# Header.net
KiCad netlist of a schematic drawn in Altium Designer
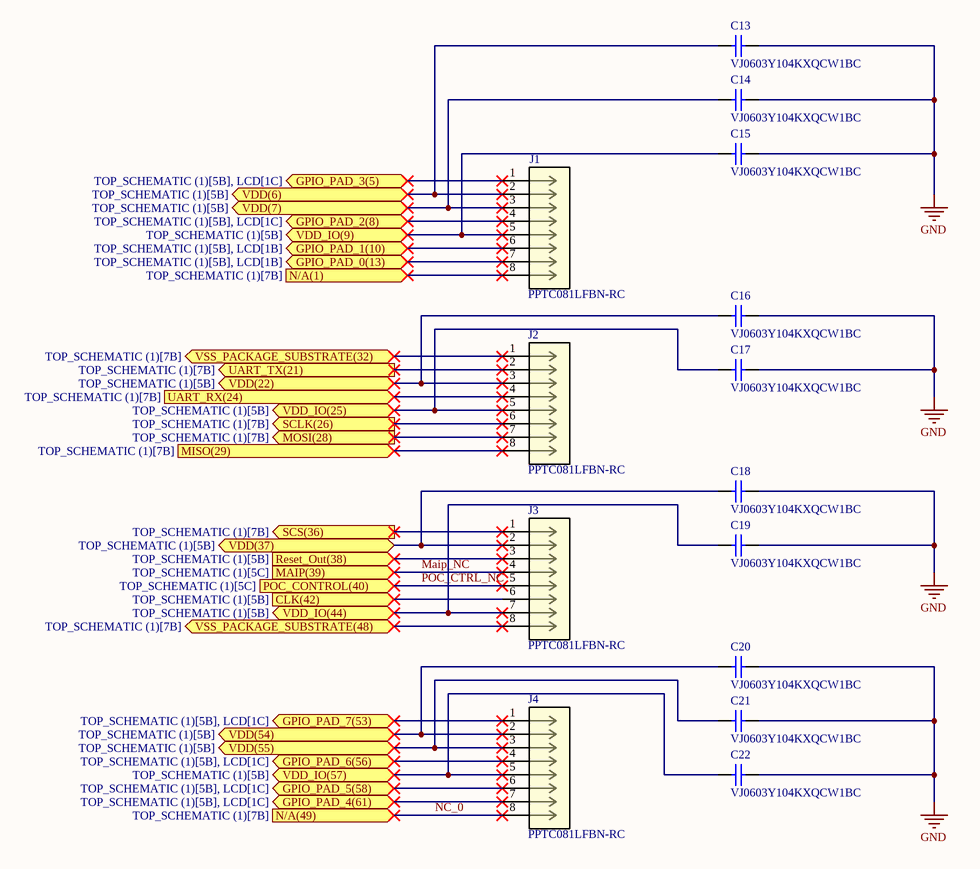
[diagram p0: Header.SchDoc]

(export (version "E")
  (design (tool "Eeschema 10.0.6"))
  (components
    (comp (ref "C13")
      (value "VJ0603Y104KXQCW1BC")
      (footprint "CAPC1608X95X40NL15T15")
      (fields (field (name "MANUFACTURER") "Vitramon"))
      (libsource (lib "Altium Content Vault") (part "CAP"))
    )
    (comp (ref "C14")
      (value "VJ0603Y104KXQCW1BC")
      (footprint "CAPC1608X95X40NL15T15")
      (fields (field (name "MANUFACTURER") "Vitramon"))
      (libsource (lib "Altium Content Vault") (part "CAP"))
    )
    (comp (ref "C15")
      (value "VJ0603Y104KXQCW1BC")
      (footprint "CAPC1608X95X40NL15T15")
      (fields (field (name "MANUFACTURER") "Vitramon"))
      (libsource (lib "Altium Content Vault") (part "CAP"))
    )
    (comp (ref "C16")
      (value "VJ0603Y104KXQCW1BC")
      (footprint "CAPC1608X95X40NL15T15")
      (fields (field (name "MANUFACTURER") "Vitramon"))
      (libsource (lib "Altium Content Vault") (part "CAP"))
    )
    (comp (ref "C17")
      (value "VJ0603Y104KXQCW1BC")
      (footprint "CAPC1608X95X40NL15T15")
      (fields (field (name "MANUFACTURER") "Vitramon"))
      (libsource (lib "Altium Content Vault") (part "CAP"))
    )
    (comp (ref "C18")
      (value "VJ0603Y104KXQCW1BC")
      (footprint "CAPC1608X95X40NL15T15")
      (fields (field (name "MANUFACTURER") "Vitramon"))
      (libsource (lib "Altium Content Vault") (part "CAP"))
    )
    (comp (ref "C19")
      (value "VJ0603Y104KXQCW1BC")
      (footprint "CAPC1608X95X40NL15T15")
      (fields (field (name "MANUFACTURER") "Vitramon"))
      (libsource (lib "Altium Content Vault") (part "CAP"))
    )
    (comp (ref "C20")
      (value "VJ0603Y104KXQCW1BC")
      (footprint "CAPC1608X95X40NL15T15")
      (fields (field (name "MANUFACTURER") "Vitramon"))
      (libsource (lib "Altium Content Vault") (part "CAP"))
    )
    (comp (ref "C21")
      (value "VJ0603Y104KXQCW1BC")
      (footprint "CAPC1608X95X40NL15T15")
      (fields (field (name "MANUFACTURER") "Vitramon"))
      (libsource (lib "Altium Content Vault") (part "CAP"))
    )
    (comp (ref "C22")
      (value "VJ0603Y104KXQCW1BC")
      (footprint "CAPC1608X95X40NL15T15")
      (fields (field (name "MANUFACTURER") "Vitramon"))
      (libsource (lib "Altium Content Vault") (part "CAP"))
    )
    (comp (ref "J1")
      (value "PPTC081LFBN-RC")
      (footprint "CONN_PPTC081LFBN-RC_SUL")
      (description "Description")
      (fields (field (name "COPYRIGHT") "Copyright (C) 2026 Ultra Librarian. All rights reserved."))
      (libsource (lib "PPTC081LFBN-RC") (part "PPTC081LFBN-RC"))
    )
    (comp (ref "J2")
      (value "PPTC081LFBN-RC")
      (footprint "CONN_PPTC081LFBN-RC_SUL")
      (description "Description")
      (fields (field (name "COPYRIGHT") "Copyright (C) 2026 Ultra Librarian. All rights reserved."))
      (libsource (lib "PPTC081LFBN-RC") (part "PPTC081LFBN-RC"))
    )
    (comp (ref "J3")
      (value "PPTC081LFBN-RC")
      (footprint "CONN_PPTC081LFBN-RC_SUL")
      (description "Description")
      (fields (field (name "COPYRIGHT") "Copyright (C) 2026 Ultra Librarian. All rights reserved."))
      (libsource (lib "PPTC081LFBN-RC") (part "PPTC081LFBN-RC"))
    )
    (comp (ref "J4")
      (value "PPTC081LFBN-RC")
      (footprint "CONN_PPTC081LFBN-RC_SUL")
      (description "Description")
      (fields (field (name "COPYRIGHT") "Copyright (C) 2026 Ultra Librarian. All rights reserved."))
      (libsource (lib "PPTC081LFBN-RC") (part "PPTC081LFBN-RC"))
    )
  )
  (nets
    (net (code "1") (name "/CLK(42)") (class "Default")
      (node (ref "J3") (pin "6") (pinfunction "6_6") (pintype "passive+no_connect"))
    )
    (net (code "2") (name "/GPIO_PAD_0(13)") (class "Default")
      (node (ref "J1") (pin "7") (pinfunction "7_7") (pintype "passive+no_connect"))
    )
    (net (code "3") (name "/GPIO_PAD_1(10)") (class "Default")
      (node (ref "J1") (pin "6") (pinfunction "6_6") (pintype "passive+no_connect"))
    )
    (net (code "4") (name "/GPIO_PAD_2(8)") (class "Default")
      (node (ref "J1") (pin "4") (pinfunction "4_4") (pintype "passive+no_connect"))
    )
    (net (code "5") (name "/GPIO_PAD_3(5)") (class "Default")
      (node (ref "J1") (pin "1") (pinfunction "1_1") (pintype "passive+no_connect"))
    )
    (net (code "6") (name "/GPIO_PAD_4(61)") (class "Default")
      (node (ref "J4") (pin "7") (pinfunction "7_7") (pintype "passive+no_connect"))
    )
    (net (code "7") (name "/GPIO_PAD_5(58)") (class "Default")
      (node (ref "J4") (pin "6") (pinfunction "6_6") (pintype "passive+no_connect"))
    )
    (net (code "8") (name "/GPIO_PAD_6(56)") (class "Default")
      (node (ref "J4") (pin "4") (pinfunction "4_4") (pintype "passive+no_connect"))
    )
    (net (code "9") (name "/GPIO_PAD_7(53)") (class "Default")
      (node (ref "J4") (pin "1") (pinfunction "1_1") (pintype "passive+no_connect"))
    )
    (net (code "10") (name "/MISO(29)") (class "Default")
      (node (ref "J2") (pin "8") (pinfunction "8_8") (pintype "passive+no_connect"))
    )
    (net (code "11") (name "/MOSI(28)") (class "Default")
      (node (ref "J2") (pin "7") (pinfunction "7_7") (pintype "passive+no_connect"))
    )
    (net (code "12") (name "/Maip_NC") (class "Default")
      (node (ref "J3") (pin "4") (pinfunction "4_4") (pintype "passive+no_connect"))
    )
    (net (code "13") (name "/NC_0") (class "Default")
      (node (ref "J4") (pin "8") (pinfunction "8_8") (pintype "passive+no_connect"))
    )
    (net (code "14") (name "/N{slash}A(1)") (class "Default")
      (node (ref "J1") (pin "8") (pinfunction "8_8") (pintype "passive+no_connect"))
    )
    (net (code "15") (name "/POC_CTRL_NC") (class "Default")
      (node (ref "J3") (pin "5") (pinfunction "5_5") (pintype "passive+no_connect"))
    )
    (net (code "16") (name "/Reset_Out(38)") (class "Default")
      (node (ref "J3") (pin "3") (pinfunction "3_3") (pintype "passive+no_connect"))
    )
    (net (code "17") (name "/SCLK(26)") (class "Default")
      (node (ref "J2") (pin "6") (pinfunction "6_6") (pintype "passive+no_connect"))
    )
    (net (code "18") (name "/SCS(36)") (class "Default")
      (node (ref "J3") (pin "1") (pinfunction "1_1") (pintype "passive+no_connect"))
    )
    (net (code "19") (name "/UART_RX(24)") (class "Default")
      (node (ref "J2") (pin "4") (pinfunction "4_4") (pintype "passive+no_connect"))
    )
    (net (code "20") (name "/UART_TX(21)") (class "Default")
      (node (ref "J2") (pin "2") (pinfunction "2_2") (pintype "passive+no_connect"))
    )
    (net (code "21") (name "/VDD(6)") (class "Default")
      (node (ref "C13") (pin "1") (pinfunction "1_1") (pintype "passive"))
      (node (ref "J1") (pin "2") (pinfunction "2_2") (pintype "passive"))
    )
    (net (code "22") (name "/VDD(7)") (class "Default")
      (node (ref "C14") (pin "1") (pinfunction "1_1") (pintype "passive"))
      (node (ref "J1") (pin "3") (pinfunction "3_3") (pintype "passive"))
    )
    (net (code "23") (name "/VDD(22)") (class "Default")
      (node (ref "C16") (pin "1") (pinfunction "1_1") (pintype "passive"))
      (node (ref "J2") (pin "3") (pinfunction "3_3") (pintype "passive"))
    )
    (net (code "24") (name "/VDD(37)") (class "Default")
      (node (ref "C18") (pin "1") (pinfunction "1_1") (pintype "passive"))
      (node (ref "J3") (pin "2") (pinfunction "2_2") (pintype "passive"))
    )
    (net (code "25") (name "/VDD(54)") (class "Default")
      (node (ref "C20") (pin "1") (pinfunction "1_1") (pintype "passive"))
      (node (ref "J4") (pin "2") (pinfunction "2_2") (pintype "passive"))
    )
    (net (code "26") (name "/VDD(55)") (class "Default")
      (node (ref "C21") (pin "1") (pinfunction "1_1") (pintype "passive"))
      (node (ref "J4") (pin "3") (pinfunction "3_3") (pintype "passive"))
    )
    (net (code "27") (name "/VDD_IO(9)") (class "Default")
      (node (ref "C15") (pin "1") (pinfunction "1_1") (pintype "passive"))
      (node (ref "J1") (pin "5") (pinfunction "5_5") (pintype "passive"))
    )
    (net (code "28") (name "/VDD_IO(25)") (class "Default")
      (node (ref "C17") (pin "1") (pinfunction "1_1") (pintype "passive"))
      (node (ref "J2") (pin "5") (pinfunction "5_5") (pintype "passive"))
    )
    (net (code "29") (name "/VDD_IO(44)") (class "Default")
      (node (ref "C19") (pin "1") (pinfunction "1_1") (pintype "passive"))
      (node (ref "J3") (pin "7") (pinfunction "7_7") (pintype "passive"))
    )
    (net (code "30") (name "/VDD_IO(57)") (class "Default")
      (node (ref "C22") (pin "1") (pinfunction "1_1") (pintype "passive"))
      (node (ref "J4") (pin "5") (pinfunction "5_5") (pintype "passive"))
    )
    (net (code "31") (name "/VSS_PACKAGE_SUBSTRATE(32)") (class "Default")
      (node (ref "J2") (pin "1") (pinfunction "1_1") (pintype "passive+no_connect"))
    )
    (net (code "32") (name "/VSS_PACKAGE_SUBSTRATE(48)") (class "Default")
      (node (ref "J3") (pin "8") (pinfunction "8_8") (pintype "passive+no_connect"))
    )
    (net (code "33") (name "GND") (class "Default")
      (node (ref "C13") (pin "2") (pinfunction "2_2") (pintype "passive"))
      (node (ref "C14") (pin "2") (pinfunction "2_2") (pintype "passive"))
      (node (ref "C15") (pin "2") (pinfunction "2_2") (pintype "passive"))
      (node (ref "C16") (pin "2") (pinfunction "2_2") (pintype "passive"))
      (node (ref "C17") (pin "2") (pinfunction "2_2") (pintype "passive"))
      (node (ref "C18") (pin "2") (pinfunction "2_2") (pintype "passive"))
      (node (ref "C19") (pin "2") (pinfunction "2_2") (pintype "passive"))
      (node (ref "C20") (pin "2") (pinfunction "2_2") (pintype "passive"))
      (node (ref "C21") (pin "2") (pinfunction "2_2") (pintype "passive"))
      (node (ref "C22") (pin "2") (pinfunction "2_2") (pintype "passive"))
    )
  )
)
